# 04_External_RAM_Interface.net
KiCad netlist of a schematic drawn in Altium Designer
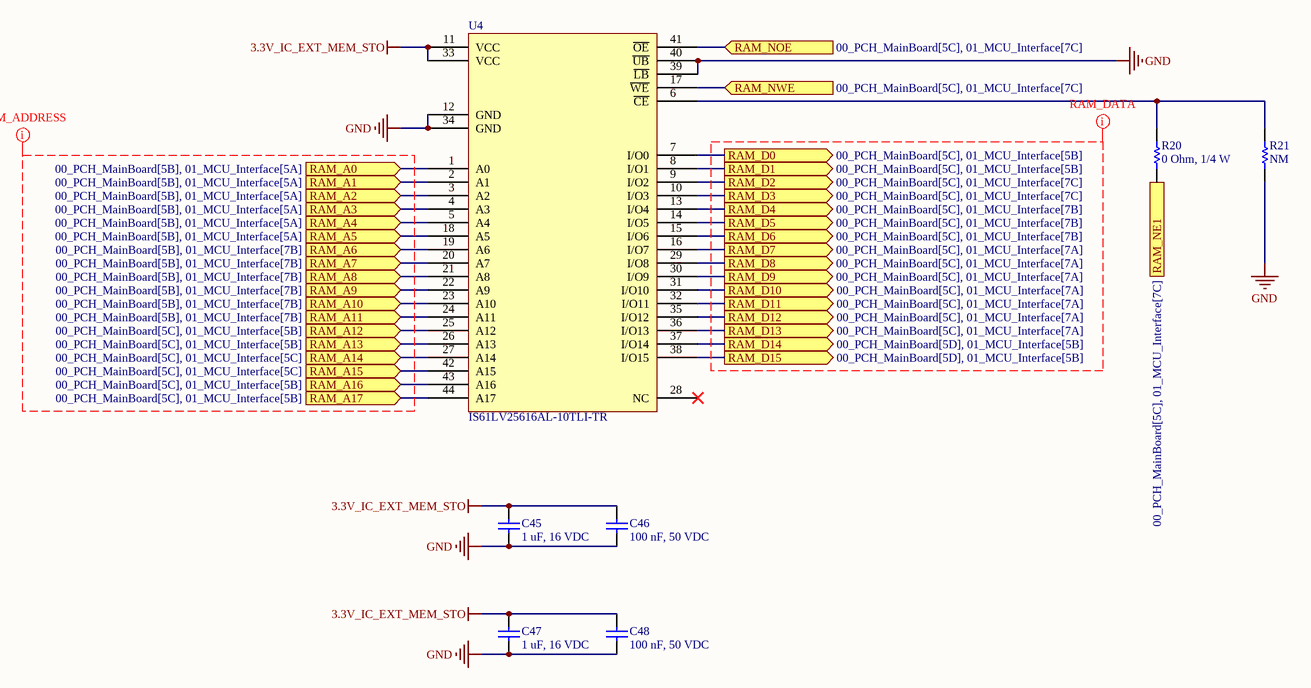
[diagram p0: 04_External_RAM_Interface.SchDoc]

(export (version "E")
  (design (tool "Eeschema 10.0.6"))
  (components
    (comp (ref "C45")
      (value "1 uF, 16 VDC")
      (footprint "CAP_0603")
      (description "CAP, size 0603, 1 uF, 16 VDC")
      (fields (field (name "TOLERANCE") "+/-10%"))
      (libsource (lib "Altium_Ceramic_Cap") (part "0106031051016"))
    )
    (comp (ref "C46")
      (value "100 nF, 50 VDC")
      (footprint "CAP_0603")
      (description "CAP, size 0603, 100 nF, 50 VDC")
      (fields (field (name "TOLERANCE") "+/-10%"))
      (libsource (lib "Altium_Ceramic_Cap") (part "0106031041050"))
    )
    (comp (ref "C47")
      (value "1 uF, 16 VDC")
      (footprint "CAP_0603")
      (description "CAP, size 0603, 1 uF, 16 VDC")
      (fields (field (name "TOLERANCE") "+/-10%"))
      (libsource (lib "Altium_Ceramic_Cap") (part "0106031051016"))
    )
    (comp (ref "C48")
      (value "100 nF, 50 VDC")
      (footprint "CAP_0603")
      (description "CAP, size 0603, 100 nF, 50 VDC")
      (fields (field (name "TOLERANCE") "+/-10%"))
      (libsource (lib "Altium_Ceramic_Cap") (part "0106031041050"))
    )
    (comp (ref "R20")
      (value "0 Ohm, 1/4 W")
      (footprint "resistor_0603")
      (description "RES, size 0603, 0 Ohm, 1/4 W")
      (libsource (lib "Altium_Resistor") (part "0006030001"))
    )
    (comp (ref "R21")
      (value "NM")
      (footprint "resistor_0603")
      (description "RES, size 0603, NM")
      (libsource (lib "Altium_Resistor") (part "000603_NM"))
    )
    (comp (ref "U4")
      (value "IS61LV25616AL-10TLI-TR")
      (footprint "IS61LV25616AL-10TLI-TR")
      (description "256K x 16 HIGH SPEED ASYNCHRONOUS CMOS STATIC RAM WITH 3.3V SUPPLY")
      (fields (field (name "MANUFACTURER") "ISSI"))
      (libsource (lib "Altium_IC") (part "IS61LV25616AL-10TLI-TR"))
    )
  )
  (nets
    (net (code "1") (name "/RAM_A0") (class "Default")
      (node (ref "U4") (pin "1") (pinfunction "A0_1") (pintype "passive"))
    )
    (net (code "2") (name "/RAM_A1") (class "Default")
      (node (ref "U4") (pin "2") (pinfunction "A1_2") (pintype "passive"))
    )
    (net (code "3") (name "/RAM_A2") (class "Default")
      (node (ref "U4") (pin "3") (pinfunction "A2_3") (pintype "passive"))
    )
    (net (code "4") (name "/RAM_A3") (class "Default")
      (node (ref "U4") (pin "4") (pinfunction "A3_4") (pintype "passive"))
    )
    (net (code "5") (name "/RAM_A4") (class "Default")
      (node (ref "U4") (pin "5") (pinfunction "A4_5") (pintype "passive"))
    )
    (net (code "6") (name "/RAM_A5") (class "Default")
      (node (ref "U4") (pin "18") (pinfunction "A5_18") (pintype "passive"))
    )
    (net (code "7") (name "/RAM_A6") (class "Default")
      (node (ref "U4") (pin "19") (pinfunction "A6_19") (pintype "passive"))
    )
    (net (code "8") (name "/RAM_A7") (class "Default")
      (node (ref "U4") (pin "20") (pinfunction "A7_20") (pintype "passive"))
    )
    (net (code "9") (name "/RAM_A8") (class "Default")
      (node (ref "U4") (pin "21") (pinfunction "A8_21") (pintype "passive"))
    )
    (net (code "10") (name "/RAM_A9") (class "Default")
      (node (ref "U4") (pin "22") (pinfunction "A9_22") (pintype "passive"))
    )
    (net (code "11") (name "/RAM_A10") (class "Default")
      (node (ref "U4") (pin "23") (pinfunction "A10_23") (pintype "passive"))
    )
    (net (code "12") (name "/RAM_A11") (class "Default")
      (node (ref "U4") (pin "24") (pinfunction "A11_24") (pintype "passive"))
    )
    (net (code "13") (name "/RAM_A12") (class "Default")
      (node (ref "U4") (pin "25") (pinfunction "A12_25") (pintype "passive"))
    )
    (net (code "14") (name "/RAM_A13") (class "Default")
      (node (ref "U4") (pin "26") (pinfunction "A13_26") (pintype "passive"))
    )
    (net (code "15") (name "/RAM_A14") (class "Default")
      (node (ref "U4") (pin "27") (pinfunction "A14_27") (pintype "passive"))
    )
    (net (code "16") (name "/RAM_A15") (class "Default")
      (node (ref "U4") (pin "42") (pinfunction "A15_42") (pintype "passive"))
    )
    (net (code "17") (name "/RAM_A16") (class "Default")
      (node (ref "U4") (pin "43") (pinfunction "A16_43") (pintype "passive"))
    )
    (net (code "18") (name "/RAM_A17") (class "Default")
      (node (ref "U4") (pin "44") (pinfunction "A17_44") (pintype "passive"))
    )
    (net (code "19") (name "/RAM_D0") (class "Default")
      (node (ref "U4") (pin "7") (pinfunction "I/O0_7") (pintype "passive"))
    )
    (net (code "20") (name "/RAM_D1") (class "Default")
      (node (ref "U4") (pin "8") (pinfunction "I/O1_8") (pintype "passive"))
    )
    (net (code "21") (name "/RAM_D2") (class "Default")
      (node (ref "U4") (pin "9") (pinfunction "I/O2_9") (pintype "passive"))
    )
    (net (code "22") (name "/RAM_D3") (class "Default")
      (node (ref "U4") (pin "10") (pinfunction "I/O3_10") (pintype "passive"))
    )
    (net (code "23") (name "/RAM_D4") (class "Default")
      (node (ref "U4") (pin "13") (pinfunction "I/O4_13") (pintype "passive"))
    )
    (net (code "24") (name "/RAM_D5") (class "Default")
      (node (ref "U4") (pin "14") (pinfunction "I/O5_14") (pintype "passive"))
    )
    (net (code "25") (name "/RAM_D6") (class "Default")
      (node (ref "U4") (pin "15") (pinfunction "I/O6_15") (pintype "passive"))
    )
    (net (code "26") (name "/RAM_D7") (class "Default")
      (node (ref "U4") (pin "16") (pinfunction "I/O7_16") (pintype "passive"))
    )
    (net (code "27") (name "/RAM_D8") (class "Default")
      (node (ref "U4") (pin "29") (pinfunction "I/O8_29") (pintype "passive"))
    )
    (net (code "28") (name "/RAM_D9") (class "Default")
      (node (ref "U4") (pin "30") (pinfunction "I/O9_30") (pintype "passive"))
    )
    (net (code "29") (name "/RAM_D10") (class "Default")
      (node (ref "U4") (pin "31") (pinfunction "I/O10_31") (pintype "passive"))
    )
    (net (code "30") (name "/RAM_D11") (class "Default")
      (node (ref "U4") (pin "32") (pinfunction "I/O11_32") (pintype "passive"))
    )
    (net (code "31") (name "/RAM_D12") (class "Default")
      (node (ref "U4") (pin "35") (pinfunction "I/O12_35") (pintype "passive"))
    )
    (net (code "32") (name "/RAM_D13") (class "Default")
      (node (ref "U4") (pin "36") (pinfunction "I/O13_36") (pintype "passive"))
    )
    (net (code "33") (name "/RAM_D14") (class "Default")
      (node (ref "U4") (pin "37") (pinfunction "I/O14_37") (pintype "passive"))
    )
    (net (code "34") (name "/RAM_D15") (class "Default")
      (node (ref "U4") (pin "38") (pinfunction "I/O15_38") (pintype "passive"))
    )
    (net (code "35") (name "/RAM_NE1") (class "Default")
      (node (ref "R20") (pin "2") (pinfunction "2_2") (pintype "passive"))
    )
    (net (code "36") (name "/RAM_NOE") (class "Default")
      (node (ref "U4") (pin "41") (pinfunction "~{OE}_41") (pintype "passive"))
    )
    (net (code "37") (name "/RAM_NWE") (class "Default")
      (node (ref "U4") (pin "17") (pinfunction "~{WE}_17") (pintype "passive"))
    )
    (net (code "38") (name "3.3V_IC_EXT_MEM_STO") (class "Default")
      (node (ref "C45") (pin "2") (pinfunction "2_2") (pintype "passive"))
      (node (ref "C46") (pin "2") (pinfunction "2_2") (pintype "passive"))
      (node (ref "C47") (pin "2") (pinfunction "2_2") (pintype "passive"))
      (node (ref "C48") (pin "2") (pinfunction "2_2") (pintype "passive"))
      (node (ref "U4") (pin "11") (pinfunction "VCC_11") (pintype "passive"))
      (node (ref "U4") (pin "33") (pinfunction "VCC_33") (pintype "passive"))
    )
    (net (code "39") (name "GND") (class "Default")
      (node (ref "C45") (pin "1") (pinfunction "1_1") (pintype "passive"))
      (node (ref "C46") (pin "1") (pinfunction "1_1") (pintype "passive"))
      (node (ref "C47") (pin "1") (pinfunction "1_1") (pintype "passive"))
      (node (ref "C48") (pin "1") (pinfunction "1_1") (pintype "passive"))
      (node (ref "R21") (pin "2") (pinfunction "2_2") (pintype "passive"))
      (node (ref "U4") (pin "12") (pinfunction "GND_12") (pintype "passive"))
      (node (ref "U4") (pin "34") (pinfunction "GND_34") (pintype "passive"))
      (node (ref "U4") (pin "39") (pinfunction "~{LB}_39") (pintype "passive"))
      (node (ref "U4") (pin "40") (pinfunction "~{UB}_40") (pintype "passive"))
    )
    (net (code "40") (name "Net-(U4-~{CE})") (class "Default")
      (node (ref "R20") (pin "1") (pinfunction "1_1") (pintype "passive"))
      (node (ref "R21") (pin "1") (pinfunction "1_1") (pintype "passive"))
      (node (ref "U4") (pin "6") (pinfunction "~{CE}_6") (pintype "passive"))
    )
    (net (code "41") (name "unconnected-(U4-NC-Pad28)") (class "Default")
      (node (ref "U4") (pin "28") (pinfunction "NC_28") (pintype "passive+no_connect"))
    )
  )
)
